# imsensor-esp-v01.net
KiCad netlist of a schematic drawn in EAGLE
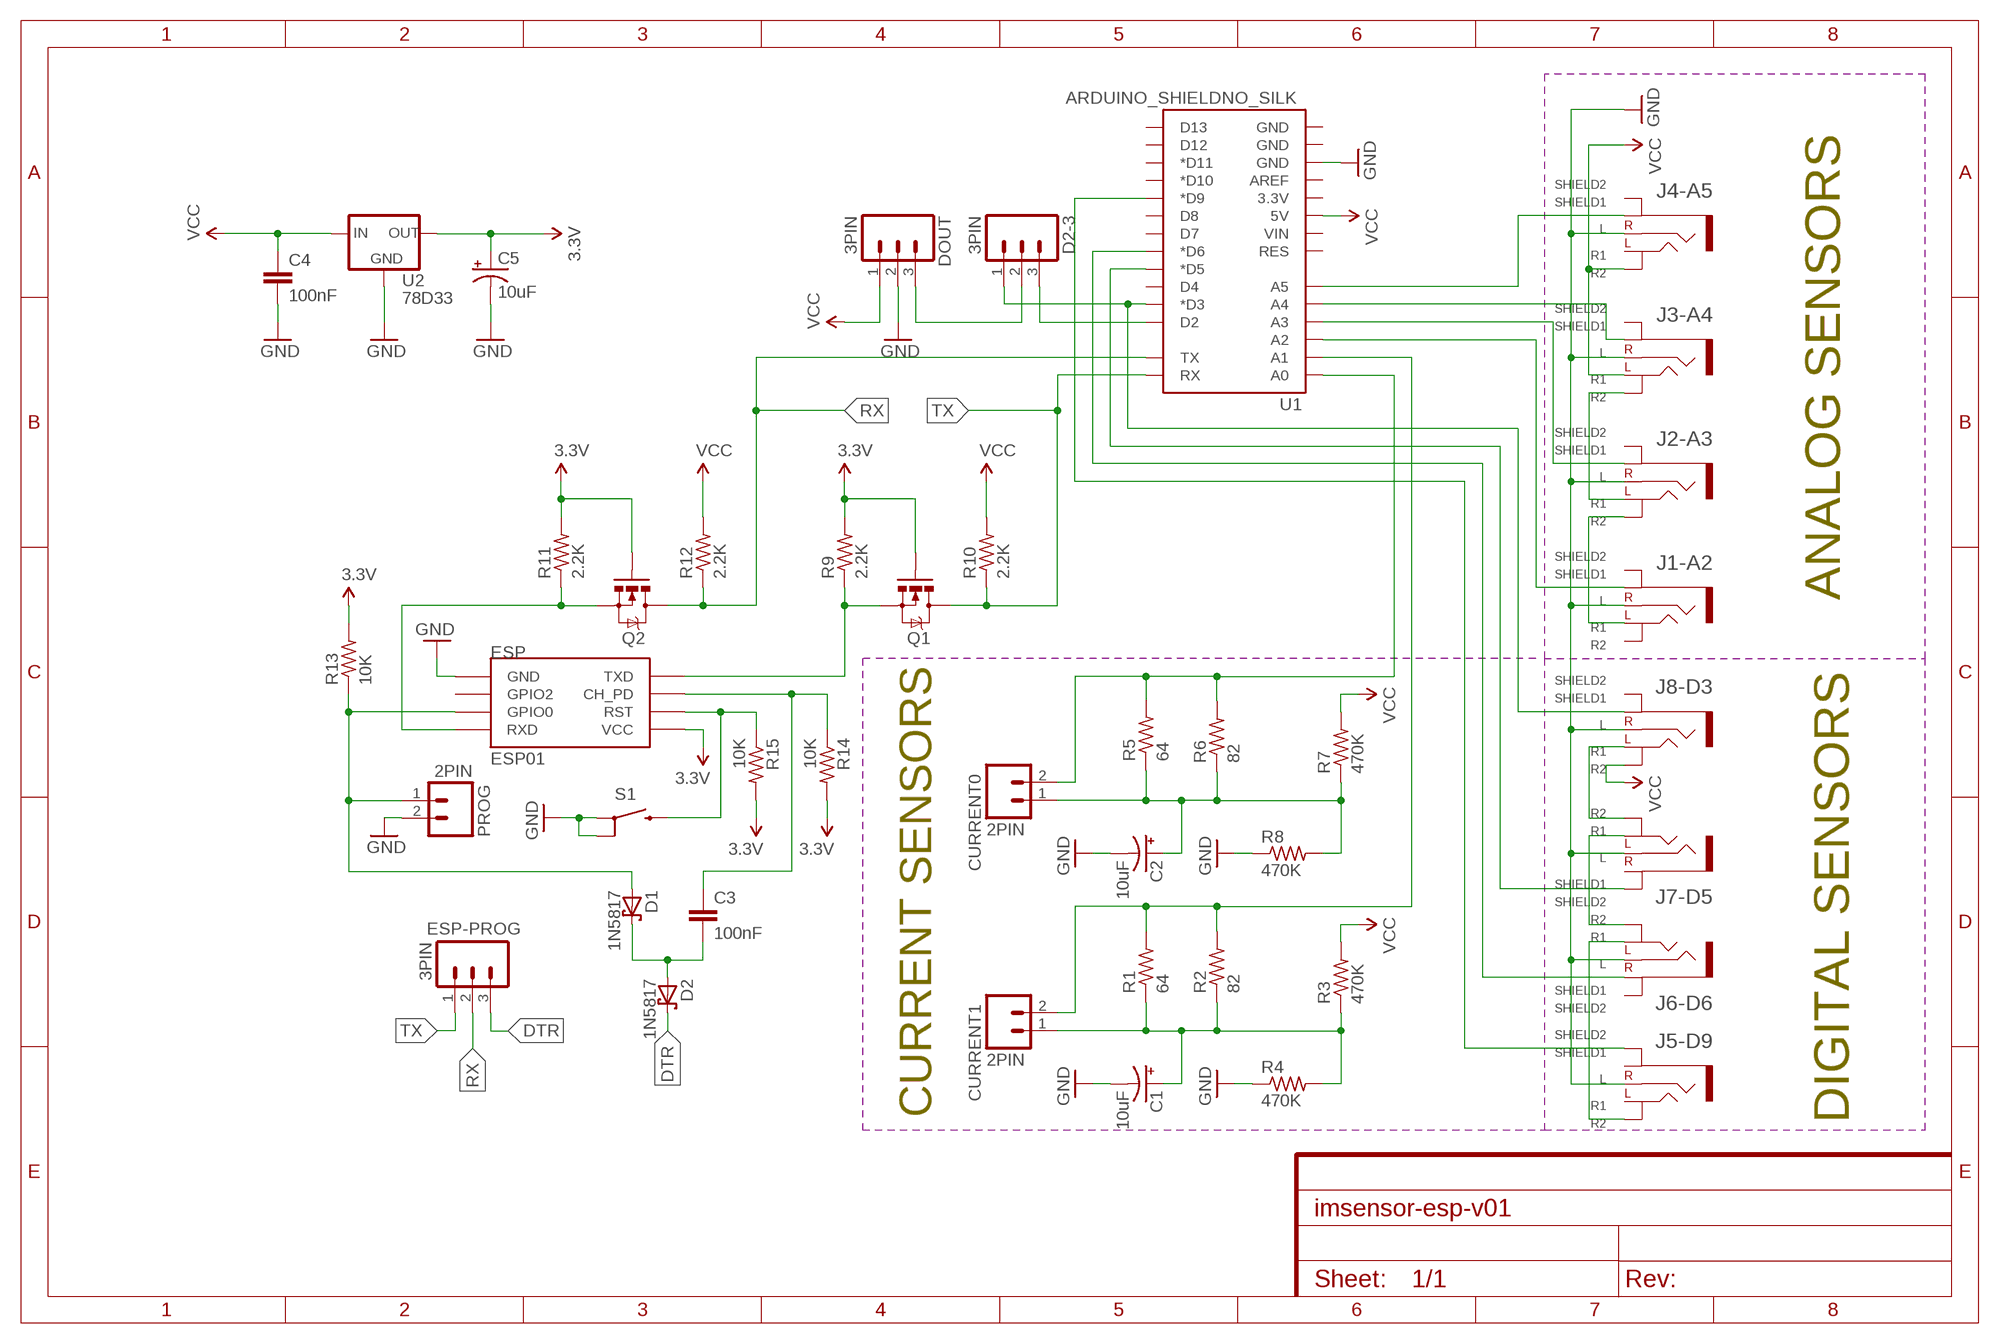
[diagram p0: schematic, sheet 1]

(export (version "E")
  (design (tool "Eeschema 10.0.6"))
  (components
    (comp (ref "C1")
      (value "10uF")
      (footprint "eagle-import:CPOL-RADIAL-10UF-25V")
      (libsource (lib "eagle-import") (part "10UF-25V-20%(PTH)"))
    )
    (comp (ref "C2")
      (value "10uF")
      (footprint "eagle-import:CPOL-RADIAL-10UF-25V")
      (libsource (lib "eagle-import") (part "10UF-25V-20%(PTH)"))
    )
    (comp (ref "C3")
      (value "100nF")
      (footprint "eagle-import:CAP-PTH-SMALL")
      (libsource (lib "eagle-import") (part "CAPPTH"))
    )
    (comp (ref "C4")
      (value "100nF")
      (footprint "eagle-import:CAP-PTH-SMALL")
      (libsource (lib "eagle-import") (part "CAPPTH"))
    )
    (comp (ref "C5")
      (value "10uF")
      (footprint "eagle-import:CPOL-RADIAL-10UF-25V")
      (libsource (lib "eagle-import") (part "10UF-25V-20%(PTH)"))
    )
    (comp (ref "CURRENT0")
      (value "2PIN")
      (footprint "eagle-import:1X02")
      (libsource (lib "eagle-import") (part "M02PTH"))
    )
    (comp (ref "CURRENT1")
      (value "2PIN")
      (footprint "eagle-import:1X02")
      (libsource (lib "eagle-import") (part "M02PTH"))
    )
    (comp (ref "D1")
      (value "1N5817")
      (footprint "eagle-import:DO41-7")
      (libsource (lib "eagle-import") (part "SCHOTTKY-DIODEDO41-7"))
    )
    (comp (ref "D2")
      (value "1N5817")
      (footprint "eagle-import:DO41-7")
      (libsource (lib "eagle-import") (part "SCHOTTKY-DIODEDO41-7"))
    )
    (comp (ref "D2-3")
      (value "3PIN")
      (footprint "eagle-import:1X03")
      (libsource (lib "eagle-import") (part "M03PTH"))
    )
    (comp (ref "DOUT")
      (value "3PIN")
      (footprint "eagle-import:1X03")
      (libsource (lib "eagle-import") (part "M03PTH"))
    )
    (comp (ref "ESP")
      (value "ESP01")
      (footprint "eagle-import:ESP01")
      (libsource (lib "eagle-import") (part "ESP01"))
    )
    (comp (ref "ESP-PROG")
      (value "3PIN")
      (footprint "eagle-import:1X03")
      (libsource (lib "eagle-import") (part "M03PTH"))
    )
    (comp (ref "J1-A2")
      (value "PJ-313-SPAD")
      (footprint "eagle-import:PJ-313-5PIN-SMALL")
      (libsource (lib "eagle-import") (part "PJ-313-SPAD"))
    )
    (comp (ref "J2-A3")
      (value "PJ-313-SPAD")
      (footprint "eagle-import:PJ-313-5PIN-SMALL")
      (libsource (lib "eagle-import") (part "PJ-313-SPAD"))
    )
    (comp (ref "J3-A4")
      (value "PJ-313-SPAD")
      (footprint "eagle-import:PJ-313-5PIN-SMALL")
      (libsource (lib "eagle-import") (part "PJ-313-SPAD"))
    )
    (comp (ref "J4-A5")
      (value "PJ-313-SPAD")
      (footprint "eagle-import:PJ-313-5PIN-SMALL")
      (libsource (lib "eagle-import") (part "PJ-313-SPAD"))
    )
    (comp (ref "J5-D9")
      (value "PJ-313-SPAD")
      (footprint "eagle-import:PJ-313-5PIN-SMALL")
      (libsource (lib "eagle-import") (part "PJ-313-SPAD"))
    )
    (comp (ref "J6-D6")
      (value "PJ-313-SPAD")
      (footprint "eagle-import:PJ-313-5PIN-SMALL")
      (libsource (lib "eagle-import") (part "PJ-313-SPAD"))
    )
    (comp (ref "J7-D5")
      (value "PJ-313-SPAD")
      (footprint "eagle-import:PJ-313-5PIN-SMALL")
      (libsource (lib "eagle-import") (part "PJ-313-SPAD"))
    )
    (comp (ref "J8-D3")
      (value "PJ-313-SPAD")
      (footprint "eagle-import:PJ-313-5PIN-SMALL")
      (libsource (lib "eagle-import") (part "PJ-313-SPAD"))
    )
    (comp (ref "PROG")
      (value "2PIN")
      (footprint "eagle-import:1X02")
      (libsource (lib "eagle-import") (part "M02PTH"))
    )
    (comp (ref "Q1")
      (value "MOSFET-NCHANNEL2N7000")
      (footprint "eagle-import:TO-92")
      (libsource (lib "eagle-import") (part "MOSFET-NCHANNEL2N7000"))
    )
    (comp (ref "Q2")
      (value "MOSFET-NCHANNEL2N7000")
      (footprint "eagle-import:TO-92")
      (libsource (lib "eagle-import") (part "MOSFET-NCHANNEL2N7000"))
    )
    (comp (ref "R1")
      (value "64")
      (footprint "eagle-import:0207_10")
      (libsource (lib "eagle-import") (part "R-US_0207/10"))
    )
    (comp (ref "R2")
      (value "82")
      (footprint "eagle-import:0207_10")
      (libsource (lib "eagle-import") (part "R-US_0207/10"))
    )
    (comp (ref "R3")
      (value "470K")
      (footprint "eagle-import:0207_10")
      (libsource (lib "eagle-import") (part "R-US_0207/10"))
    )
    (comp (ref "R4")
      (value "470K")
      (footprint "eagle-import:0207_10")
      (libsource (lib "eagle-import") (part "R-US_0207/10"))
    )
    (comp (ref "R5")
      (value "64")
      (footprint "eagle-import:0207_10")
      (libsource (lib "eagle-import") (part "R-US_0207/10"))
    )
    (comp (ref "R6")
      (value "82")
      (footprint "eagle-import:0207_10")
      (libsource (lib "eagle-import") (part "R-US_0207/10"))
    )
    (comp (ref "R7")
      (value "470K")
      (footprint "eagle-import:0207_10")
      (libsource (lib "eagle-import") (part "R-US_0207/10"))
    )
    (comp (ref "R8")
      (value "470K")
      (footprint "eagle-import:0207_10")
      (libsource (lib "eagle-import") (part "R-US_0207/10"))
    )
    (comp (ref "R9")
      (value "2.2K")
      (footprint "eagle-import:0207_10")
      (libsource (lib "eagle-import") (part "R-US_0207/10"))
    )
    (comp (ref "R10")
      (value "2.2K")
      (footprint "eagle-import:0207_10")
      (libsource (lib "eagle-import") (part "R-US_0207/10"))
    )
    (comp (ref "R11")
      (value "2.2K")
      (footprint "eagle-import:0207_10")
      (libsource (lib "eagle-import") (part "R-US_0207/10"))
    )
    (comp (ref "R12")
      (value "2.2K")
      (footprint "eagle-import:0207_10")
      (libsource (lib "eagle-import") (part "R-US_0207/10"))
    )
    (comp (ref "R13")
      (value "10K")
      (footprint "eagle-import:0207_10")
      (libsource (lib "eagle-import") (part "R-US_0207/10"))
    )
    (comp (ref "R14")
      (value "10K")
      (footprint "eagle-import:0207_10")
      (libsource (lib "eagle-import") (part "R-US_0207/10"))
    )
    (comp (ref "R15")
      (value "10K")
      (footprint "eagle-import:0207_10")
      (libsource (lib "eagle-import") (part "R-US_0207/10"))
    )
    (comp (ref "S1")
      (value "SWITCH-MOMENTARY-2PTH")
      (footprint "eagle-import:TACTILE-PTH")
      (libsource (lib "eagle-import") (part "SWITCH-MOMENTARY-2PTH"))
    )
    (comp (ref "U1")
      (value "ARDUINO_SHIELDNO_SILK")
      (footprint "eagle-import:DUEMILANOVE_VIAS")
      (libsource (lib "eagle-import") (part "ARDUINO_SHIELDNO_SILK"))
    )
    (comp (ref "U2")
      (value "78D33")
      (footprint "eagle-import:TO220-IGO")
      (libsource (lib "eagle-import") (part "V_REG_78XXSINK"))
    )
  )
  (nets
    (net (code "1") (name "3.3V") (class "Default")
      (node (ref "C5") (pin "1") (pinfunction "+_1") (pintype "passive"))
      (node (ref "ESP") (pin "VCC") (pinfunction "VCC_VCC") (pintype "bidirectional"))
      (node (ref "Q1") (pin "2") (pinfunction "G_2") (pintype "passive"))
      (node (ref "Q2") (pin "2") (pinfunction "G_2") (pintype "passive"))
      (node (ref "R11") (pin "2") (pinfunction "2_2") (pintype "passive"))
      (node (ref "R13") (pin "2") (pinfunction "2_2") (pintype "passive"))
      (node (ref "R14") (pin "2") (pinfunction "2_2") (pintype "passive"))
      (node (ref "R15") (pin "2") (pinfunction "2_2") (pintype "passive"))
      (node (ref "R9") (pin "2") (pinfunction "2_2") (pintype "passive"))
      (node (ref "U2") (pin "OUT") (pinfunction "OUT_OUT") (pintype "passive"))
    )
    (net (code "2") (name "DTR") (class "Default")
      (node (ref "D2") (pin "C") (pinfunction "C_C") (pintype "passive"))
      (node (ref "ESP-PROG") (pin "3") (pinfunction "3_3") (pintype "passive"))
    )
    (net (code "3") (name "GND") (class "Default")
      (node (ref "C1") (pin "2") (pinfunction "-_2") (pintype "passive"))
      (node (ref "C2") (pin "2") (pinfunction "-_2") (pintype "passive"))
      (node (ref "C4") (pin "2") (pinfunction "2_2") (pintype "passive"))
      (node (ref "C5") (pin "2") (pinfunction "-_2") (pintype "passive"))
      (node (ref "DOUT") (pin "2") (pinfunction "2_2") (pintype "passive"))
      (node (ref "ESP") (pin "GND") (pinfunction "GND_GND") (pintype "bidirectional"))
      (node (ref "J1-A2") (pin "2") (pinfunction "R_2") (pintype "bidirectional"))
      (node (ref "J2-A3") (pin "2") (pinfunction "R_2") (pintype "bidirectional"))
      (node (ref "J3-A4") (pin "2") (pinfunction "R_2") (pintype "bidirectional"))
      (node (ref "J4-A5") (pin "2") (pinfunction "R_2") (pintype "bidirectional"))
      (node (ref "J5-D9") (pin "2") (pinfunction "R_2") (pintype "bidirectional"))
      (node (ref "J6-D6") (pin "2") (pinfunction "R_2") (pintype "bidirectional"))
      (node (ref "J7-D5") (pin "2") (pinfunction "R_2") (pintype "bidirectional"))
      (node (ref "J8-D3") (pin "2") (pinfunction "R_2") (pintype "bidirectional"))
      (node (ref "PROG") (pin "2") (pinfunction "2_2") (pintype "passive"))
      (node (ref "R4") (pin "1") (pinfunction "1_1") (pintype "passive"))
      (node (ref "R8") (pin "1") (pinfunction "1_1") (pintype "passive"))
      (node (ref "S1") (pin "1") (pinfunction "1_1") (pintype "passive"))
      (node (ref "S1") (pin "2") (pinfunction "P$1_2") (pintype "passive"))
      (node (ref "U1") (pin "GND@2") (pinfunction "GND_GND@2") (pintype "bidirectional"))
      (node (ref "U2") (pin "GND") (pinfunction "GND_GND") (pintype "input"))
    )
    (net (code "4") (name "Net-(C1-+)") (class "Default")
      (node (ref "C1") (pin "1") (pinfunction "+_1") (pintype "passive"))
      (node (ref "CURRENT1") (pin "1") (pinfunction "1_1") (pintype "passive"))
      (node (ref "R1") (pin "1") (pinfunction "1_1") (pintype "passive"))
      (node (ref "R2") (pin "1") (pinfunction "1_1") (pintype "passive"))
      (node (ref "R3") (pin "1") (pinfunction "1_1") (pintype "passive"))
      (node (ref "R4") (pin "2") (pinfunction "2_2") (pintype "passive"))
    )
    (net (code "5") (name "Net-(C2-+)") (class "Default")
      (node (ref "C2") (pin "1") (pinfunction "+_1") (pintype "passive"))
      (node (ref "CURRENT0") (pin "1") (pinfunction "1_1") (pintype "passive"))
      (node (ref "R5") (pin "1") (pinfunction "1_1") (pintype "passive"))
      (node (ref "R6") (pin "1") (pinfunction "1_1") (pintype "passive"))
      (node (ref "R7") (pin "1") (pinfunction "1_1") (pintype "passive"))
      (node (ref "R8") (pin "2") (pinfunction "2_2") (pintype "passive"))
    )
    (net (code "6") (name "Net-(C3-Pad1)") (class "Default")
      (node (ref "C3") (pin "1") (pinfunction "1_1") (pintype "passive"))
      (node (ref "ESP") (pin "CH_PD") (pinfunction "CH_PD_CH_PD") (pintype "bidirectional"))
      (node (ref "R14") (pin "1") (pinfunction "1_1") (pintype "passive"))
    )
    (net (code "7") (name "Net-(C3-Pad2)") (class "Default")
      (node (ref "C3") (pin "2") (pinfunction "2_2") (pintype "passive"))
      (node (ref "D1") (pin "C") (pinfunction "C_C") (pintype "passive"))
      (node (ref "D2") (pin "A") (pinfunction "A_A") (pintype "passive"))
    )
    (net (code "8") (name "Net-(CURRENT0-Pad2)") (class "Default")
      (node (ref "CURRENT0") (pin "2") (pinfunction "2_2") (pintype "passive"))
      (node (ref "R5") (pin "2") (pinfunction "2_2") (pintype "passive"))
      (node (ref "R6") (pin "2") (pinfunction "2_2") (pintype "passive"))
      (node (ref "U1") (pin "A0") (pinfunction "A0_A0") (pintype "bidirectional"))
    )
    (net (code "9") (name "Net-(CURRENT1-Pad2)") (class "Default")
      (node (ref "CURRENT1") (pin "2") (pinfunction "2_2") (pintype "passive"))
      (node (ref "R1") (pin "2") (pinfunction "2_2") (pintype "passive"))
      (node (ref "R2") (pin "2") (pinfunction "2_2") (pintype "passive"))
      (node (ref "U1") (pin "A1") (pinfunction "A1_A1") (pintype "bidirectional"))
    )
    (net (code "10") (name "Net-(D1-PadA)") (class "Default")
      (node (ref "D1") (pin "A") (pinfunction "A_A") (pintype "passive"))
      (node (ref "ESP") (pin "GPIO0") (pinfunction "GPIO0_GPIO0") (pintype "bidirectional"))
      (node (ref "PROG") (pin "1") (pinfunction "1_1") (pintype "passive"))
      (node (ref "R13") (pin "1") (pinfunction "1_1") (pintype "passive"))
    )
    (net (code "11") (name "Net-(D2-3-Pad2)") (class "Default")
      (node (ref "D2-3") (pin "2") (pinfunction "2_2") (pintype "passive"))
      (node (ref "DOUT") (pin "3") (pinfunction "3_3") (pintype "passive"))
    )
    (net (code "12") (name "Net-(D2-3-Pad3)") (class "Default")
      (node (ref "D2-3") (pin "3") (pinfunction "3_3") (pintype "passive"))
      (node (ref "U1") (pin "D2") (pinfunction "D2_D2") (pintype "bidirectional"))
    )
    (net (code "13") (name "Net-(ESP-RXD)") (class "Default")
      (node (ref "ESP") (pin "RX") (pinfunction "RXD_RX") (pintype "bidirectional"))
      (node (ref "Q2") (pin "1") (pinfunction "S_1") (pintype "passive"))
      (node (ref "R11") (pin "1") (pinfunction "1_1") (pintype "passive"))
    )
    (net (code "14") (name "Net-(ESP-TXD)") (class "Default")
      (node (ref "ESP") (pin "TX") (pinfunction "TXD_TX") (pintype "bidirectional"))
      (node (ref "Q1") (pin "1") (pinfunction "S_1") (pintype "passive"))
      (node (ref "R9") (pin "1") (pinfunction "1_1") (pintype "passive"))
    )
    (net (code "15") (name "Net-(J1-A2-L1)") (class "Default")
      (node (ref "J1-A2") (pin "3.1") (pinfunction "L1_3.1") (pintype "bidirectional"))
      (node (ref "J2-A3") (pin "3.2") (pinfunction "L2_3.2") (pintype "bidirectional"))
    )
    (net (code "16") (name "Net-(J1-A2-SHIELD1)") (class "Default")
      (node (ref "J1-A2") (pin "1.1") (pinfunction "SHIELD1_1.1") (pintype "bidirectional"))
      (node (ref "U1") (pin "A2") (pinfunction "A2_A2") (pintype "bidirectional"))
    )
    (net (code "17") (name "Net-(J2-A3-L1)") (class "Default")
      (node (ref "J2-A3") (pin "3.1") (pinfunction "L1_3.1") (pintype "bidirectional"))
      (node (ref "J3-A4") (pin "3.2") (pinfunction "L2_3.2") (pintype "bidirectional"))
    )
    (net (code "18") (name "Net-(J2-A3-SHIELD1)") (class "Default")
      (node (ref "J2-A3") (pin "1.1") (pinfunction "SHIELD1_1.1") (pintype "bidirectional"))
      (node (ref "U1") (pin "A3") (pinfunction "A3_A3") (pintype "bidirectional"))
    )
    (net (code "19") (name "Net-(J3-A4-SHIELD1)") (class "Default")
      (node (ref "J3-A4") (pin "1.1") (pinfunction "SHIELD1_1.1") (pintype "bidirectional"))
      (node (ref "U1") (pin "A4") (pinfunction "A4_A4") (pintype "bidirectional"))
    )
    (net (code "20") (name "Net-(J4-A5-SHIELD1)") (class "Default")
      (node (ref "J4-A5") (pin "1.1") (pinfunction "SHIELD1_1.1") (pintype "bidirectional"))
      (node (ref "U1") (pin "A5") (pinfunction "A5_A5") (pintype "bidirectional"))
    )
    (net (code "21") (name "Net-(J5-D9-L2)") (class "Default")
      (node (ref "J5-D9") (pin "3.2") (pinfunction "L2_3.2") (pintype "bidirectional"))
      (node (ref "J6-D6") (pin "3.1") (pinfunction "L1_3.1") (pintype "bidirectional"))
    )
    (net (code "22") (name "Net-(J5-D9-SHIELD2)") (class "Default")
      (node (ref "J5-D9") (pin "1.2") (pinfunction "SHIELD2_1.2") (pintype "bidirectional"))
      (node (ref "U1") (pin "D9") (pinfunction "*D9_D9") (pintype "bidirectional"))
    )
    (net (code "23") (name "Net-(J6-D6-L2)") (class "Default")
      (node (ref "J6-D6") (pin "3.2") (pinfunction "L2_3.2") (pintype "bidirectional"))
      (node (ref "J7-D5") (pin "3.1") (pinfunction "L1_3.1") (pintype "bidirectional"))
    )
    (net (code "24") (name "Net-(J6-D6-SHIELD1)") (class "Default")
      (node (ref "J6-D6") (pin "1.1") (pinfunction "SHIELD1_1.1") (pintype "bidirectional"))
      (node (ref "U1") (pin "D6") (pinfunction "*D6_D6") (pintype "bidirectional"))
    )
    (net (code "25") (name "Net-(J7-D5-L2)") (class "Default")
      (node (ref "J7-D5") (pin "3.2") (pinfunction "L2_3.2") (pintype "bidirectional"))
      (node (ref "J8-D3") (pin "3.1") (pinfunction "L1_3.1") (pintype "bidirectional"))
    )
    (net (code "26") (name "Net-(J7-D5-SHIELD2)") (class "Default")
      (node (ref "J7-D5") (pin "1.2") (pinfunction "SHIELD2_1.2") (pintype "bidirectional"))
      (node (ref "U1") (pin "D5") (pinfunction "*D5_D5") (pintype "bidirectional"))
    )
    (net (code "27") (name "Net-(J8-D3-SHIELD1)") (class "Default")
      (node (ref "D2-3") (pin "1") (pinfunction "1_1") (pintype "passive"))
      (node (ref "J8-D3") (pin "1.1") (pinfunction "SHIELD1_1.1") (pintype "bidirectional"))
      (node (ref "U1") (pin "D3") (pinfunction "*D3_D3") (pintype "bidirectional"))
    )
    (net (code "28") (name "Net-(S1-2)") (class "Default")
      (node (ref "ESP") (pin "RST") (pinfunction "RST_RST") (pintype "bidirectional"))
      (node (ref "R15") (pin "1") (pinfunction "1_1") (pintype "passive"))
      (node (ref "S1") (pin "3") (pinfunction "2_3") (pintype "passive"))
    )
    (net (code "29") (name "RX") (class "Default")
      (node (ref "ESP-PROG") (pin "2") (pinfunction "2_2") (pintype "passive"))
      (node (ref "Q2") (pin "3") (pinfunction "D_3") (pintype "passive"))
      (node (ref "R12") (pin "1") (pinfunction "1_1") (pintype "passive"))
      (node (ref "U1") (pin "TX") (pinfunction "TX_TX") (pintype "bidirectional"))
    )
    (net (code "30") (name "TX") (class "Default")
      (node (ref "ESP-PROG") (pin "1") (pinfunction "1_1") (pintype "passive"))
      (node (ref "Q1") (pin "3") (pinfunction "D_3") (pintype "passive"))
      (node (ref "R10") (pin "1") (pinfunction "1_1") (pintype "passive"))
      (node (ref "U1") (pin "RX") (pinfunction "RX_RX") (pintype "bidirectional"))
    )
    (net (code "31") (name "VCC") (class "Default")
      (node (ref "C4") (pin "1") (pinfunction "1_1") (pintype "passive"))
      (node (ref "DOUT") (pin "1") (pinfunction "1_1") (pintype "passive"))
      (node (ref "J3-A4") (pin "3.1") (pinfunction "L1_3.1") (pintype "bidirectional"))
      (node (ref "J4-A5") (pin "3.2") (pinfunction "L2_3.2") (pintype "bidirectional"))
      (node (ref "J8-D3") (pin "3.2") (pinfunction "L2_3.2") (pintype "bidirectional"))
      (node (ref "R10") (pin "2") (pinfunction "2_2") (pintype "passive"))
      (node (ref "R12") (pin "2") (pinfunction "2_2") (pintype "passive"))
      (node (ref "R3") (pin "2") (pinfunction "2_2") (pintype "passive"))
      (node (ref "R7") (pin "2") (pinfunction "2_2") (pintype "passive"))
      (node (ref "U1") (pin "5V") (pinfunction "5V_5V") (pintype "bidirectional"))
      (node (ref "U2") (pin "IN") (pinfunction "IN_IN") (pintype "input"))
    )
    (net (code "32") (name "unconnected-(ESP-PadGPIO2)") (class "Default")
      (node (ref "ESP") (pin "GPIO2") (pinfunction "GPIO2_GPIO2") (pintype "bidirectional"))
    )
    (net (code "33") (name "unconnected-(J1-A2-L2-Pad3.2)") (class "Default")
      (node (ref "J1-A2") (pin "3.2") (pinfunction "L2_3.2") (pintype "bidirectional"))
    )
    (net (code "34") (name "unconnected-(J1-A2-SHIELD2-Pad1.2)") (class "Default")
      (node (ref "J1-A2") (pin "1.2") (pinfunction "SHIELD2_1.2") (pintype "bidirectional"))
    )
    (net (code "35") (name "unconnected-(J2-A3-SHIELD2-Pad1.2)") (class "Default")
      (node (ref "J2-A3") (pin "1.2") (pinfunction "SHIELD2_1.2") (pintype "bidirectional"))
    )
    (net (code "36") (name "unconnected-(J3-A4-SHIELD2-Pad1.2)") (class "Default")
      (node (ref "J3-A4") (pin "1.2") (pinfunction "SHIELD2_1.2") (pintype "bidirectional"))
    )
    (net (code "37") (name "unconnected-(J4-A5-L1-Pad3.1)") (class "Default")
      (node (ref "J4-A5") (pin "3.1") (pinfunction "L1_3.1") (pintype "bidirectional"))
    )
    (net (code "38") (name "unconnected-(J4-A5-SHIELD2-Pad1.2)") (class "Default")
      (node (ref "J4-A5") (pin "1.2") (pinfunction "SHIELD2_1.2") (pintype "bidirectional"))
    )
    (net (code "39") (name "unconnected-(J5-D9-L1-Pad3.1)") (class "Default")
      (node (ref "J5-D9") (pin "3.1") (pinfunction "L1_3.1") (pintype "bidirectional"))
    )
    (net (code "40") (name "unconnected-(J5-D9-SHIELD1-Pad1.1)") (class "Default")
      (node (ref "J5-D9") (pin "1.1") (pinfunction "SHIELD1_1.1") (pintype "bidirectional"))
    )
    (net (code "41") (name "unconnected-(J6-D6-SHIELD2-Pad1.2)") (class "Default")
      (node (ref "J6-D6") (pin "1.2") (pinfunction "SHIELD2_1.2") (pintype "bidirectional"))
    )
    (net (code "42") (name "unconnected-(J7-D5-SHIELD1-Pad1.1)") (class "Default")
      (node (ref "J7-D5") (pin "1.1") (pinfunction "SHIELD1_1.1") (pintype "bidirectional"))
    )
    (net (code "43") (name "unconnected-(J8-D3-SHIELD2-Pad1.2)") (class "Default")
      (node (ref "J8-D3") (pin "1.2") (pinfunction "SHIELD2_1.2") (pintype "bidirectional"))
    )
    (net (code "44") (name "unconnected-(U1-*D10-PadD10)") (class "Default")
      (node (ref "U1") (pin "D10") (pinfunction "*D10_D10") (pintype "bidirectional"))
    )
    (net (code "45") (name "unconnected-(U1-*D11-PadD11)") (class "Default")
      (node (ref "U1") (pin "D11") (pinfunction "*D11_D11") (pintype "bidirectional"))
    )
    (net (code "46") (name "unconnected-(U1-GND-PadGND@0)") (class "Default")
      (node (ref "U1") (pin "GND@0") (pinfunction "GND_GND@0") (pintype "bidirectional"))
    )
    (net (code "47") (name "unconnected-(U1-GND-PadGND@1)") (class "Default")
      (node (ref "U1") (pin "GND@1") (pinfunction "GND_GND@1") (pintype "bidirectional"))
    )
    (net (code "48") (name "unconnected-(U1-Pad3.3V)") (class "Default")
      (node (ref "U1") (pin "3.3V") (pinfunction "3.3V_3.3V") (pintype "bidirectional"))
    )
    (net (code "49") (name "unconnected-(U1-PadAREF)") (class "Default")
      (node (ref "U1") (pin "AREF") (pinfunction "AREF_AREF") (pintype "bidirectional"))
    )
    (net (code "50") (name "unconnected-(U1-PadD4)") (class "Default")
      (node (ref "U1") (pin "D4") (pinfunction "D4_D4") (pintype "bidirectional"))
    )
    (net (code "51") (name "unconnected-(U1-PadD7)") (class "Default")
      (node (ref "U1") (pin "D7") (pinfunction "D7_D7") (pintype "bidirectional"))
    )
    (net (code "52") (name "unconnected-(U1-PadD8)") (class "Default")
      (node (ref "U1") (pin "D8") (pinfunction "D8_D8") (pintype "bidirectional"))
    )
    (net (code "53") (name "unconnected-(U1-PadD12)") (class "Default")
      (node (ref "U1") (pin "D12") (pinfunction "D12_D12") (pintype "bidirectional"))
    )
    (net (code "54") (name "unconnected-(U1-PadD13)") (class "Default")
      (node (ref "U1") (pin "D13") (pinfunction "D13_D13") (pintype "bidirectional"))
    )
    (net (code "55") (name "unconnected-(U1-PadRES)") (class "Default")
      (node (ref "U1") (pin "RES") (pinfunction "RES_RES") (pintype "bidirectional"))
    )
    (net (code "56") (name "unconnected-(U1-PadVIN)") (class "Default")
      (node (ref "U1") (pin "VIN") (pinfunction "VIN_VIN") (pintype "bidirectional"))
    )
  )
)
